# untitled.net
KiCad netlist of a schematic drawn in EAGLE
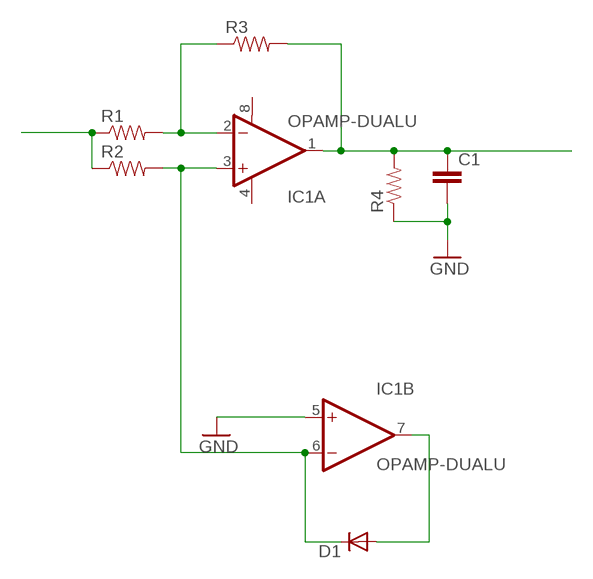
[diagram p0: schematic, sheet 1]

(export (version "E")
  (design (tool "Eeschema 10.0.6"))
  (components
    (comp (ref "C1")
      (value "CAP_")
      (footprint "eagle-import:AXIAL-5MM")
      (libsource (lib "eagle-import") (part "CAP_"))
    )
    (comp (ref "D1")
      (value "DIODEPTH")
      (footprint "eagle-import:DIODE-1N4001")
      (libsource (lib "eagle-import") (part "DIODEPTH"))
    )
    (comp (ref "IC1")
      (value "OPAMP-DUALU")
      (footprint "eagle-import:SO08")
      (libsource (lib "eagle-import") (part "OPAMP-DUALU"))
    )
    (comp (ref "R1")
      (value "RESISTORPTH-1/6W")
      (footprint "eagle-import:1_6W-RES")
      (libsource (lib "eagle-import") (part "RESISTORPTH-1/6W"))
    )
    (comp (ref "R2")
      (value "RESISTORPTH-1/6W")
      (footprint "eagle-import:1_6W-RES")
      (libsource (lib "eagle-import") (part "RESISTORPTH-1/6W"))
    )
    (comp (ref "R3")
      (value "RESISTORPTH-1/6W")
      (footprint "eagle-import:1_6W-RES")
      (libsource (lib "eagle-import") (part "RESISTORPTH-1/6W"))
    )
    (comp (ref "R4")
      (value "RESISTORPTH-1/6W")
      (footprint "eagle-import:1_6W-RES")
      (libsource (lib "eagle-import") (part "RESISTORPTH-1/6W"))
    )
  )
  (nets
    (net (code "1") (name "/V+") (class "Default")
      (node (ref "IC1") (pin "8") (pinfunction "V+_8") (pintype "power_in"))
    )
    (net (code "2") (name "/V-") (class "Default")
      (node (ref "IC1") (pin "4") (pinfunction "V-_4") (pintype "power_in"))
    )
    (net (code "3") (name "GND") (class "Default")
      (node (ref "C1") (pin "P$2") (pinfunction "2_P$2") (pintype "passive"))
      (node (ref "IC1") (pin "5") (pinfunction "+IN_5") (pintype "input"))
      (node (ref "R4") (pin "1") (pinfunction "1_1") (pintype "passive"))
    )
    (net (code "4") (name "Net-(C1-1)") (class "Default")
      (node (ref "C1") (pin "P$1") (pinfunction "1_P$1") (pintype "passive"))
      (node (ref "IC1") (pin "1") (pinfunction "OUT_1") (pintype "output"))
      (node (ref "R3") (pin "2") (pinfunction "2_2") (pintype "passive"))
      (node (ref "R4") (pin "2") (pinfunction "2_2") (pintype "passive"))
    )
    (net (code "5") (name "Net-(IC1A-+IN)") (class "Default")
      (node (ref "D1") (pin "C") (pinfunction "C_C") (pintype "passive"))
      (node (ref "IC1") (pin "3") (pinfunction "+IN_3") (pintype "input"))
      (node (ref "IC1") (pin "6") (pinfunction "-IN_6") (pintype "input"))
      (node (ref "R2") (pin "2") (pinfunction "2_2") (pintype "passive"))
    )
    (net (code "6") (name "Net-(IC1A--IN)") (class "Default")
      (node (ref "IC1") (pin "2") (pinfunction "-IN_2") (pintype "input"))
      (node (ref "R1") (pin "2") (pinfunction "2_2") (pintype "passive"))
      (node (ref "R3") (pin "1") (pinfunction "1_1") (pintype "passive"))
    )
    (net (code "7") (name "Net-(IC1B-OUT)") (class "Default")
      (node (ref "D1") (pin "A") (pinfunction "A_A") (pintype "passive"))
      (node (ref "IC1") (pin "7") (pinfunction "OUT_7") (pintype "output"))
    )
    (net (code "8") (name "Net-(R1-Pad1)") (class "Default")
      (node (ref "R1") (pin "1") (pinfunction "1_1") (pintype "passive"))
      (node (ref "R2") (pin "1") (pinfunction "1_1") (pintype "passive"))
    )
  )
)
